# SIT210-_Project.net
KiCad netlist of a schematic drawn in EasyEDA
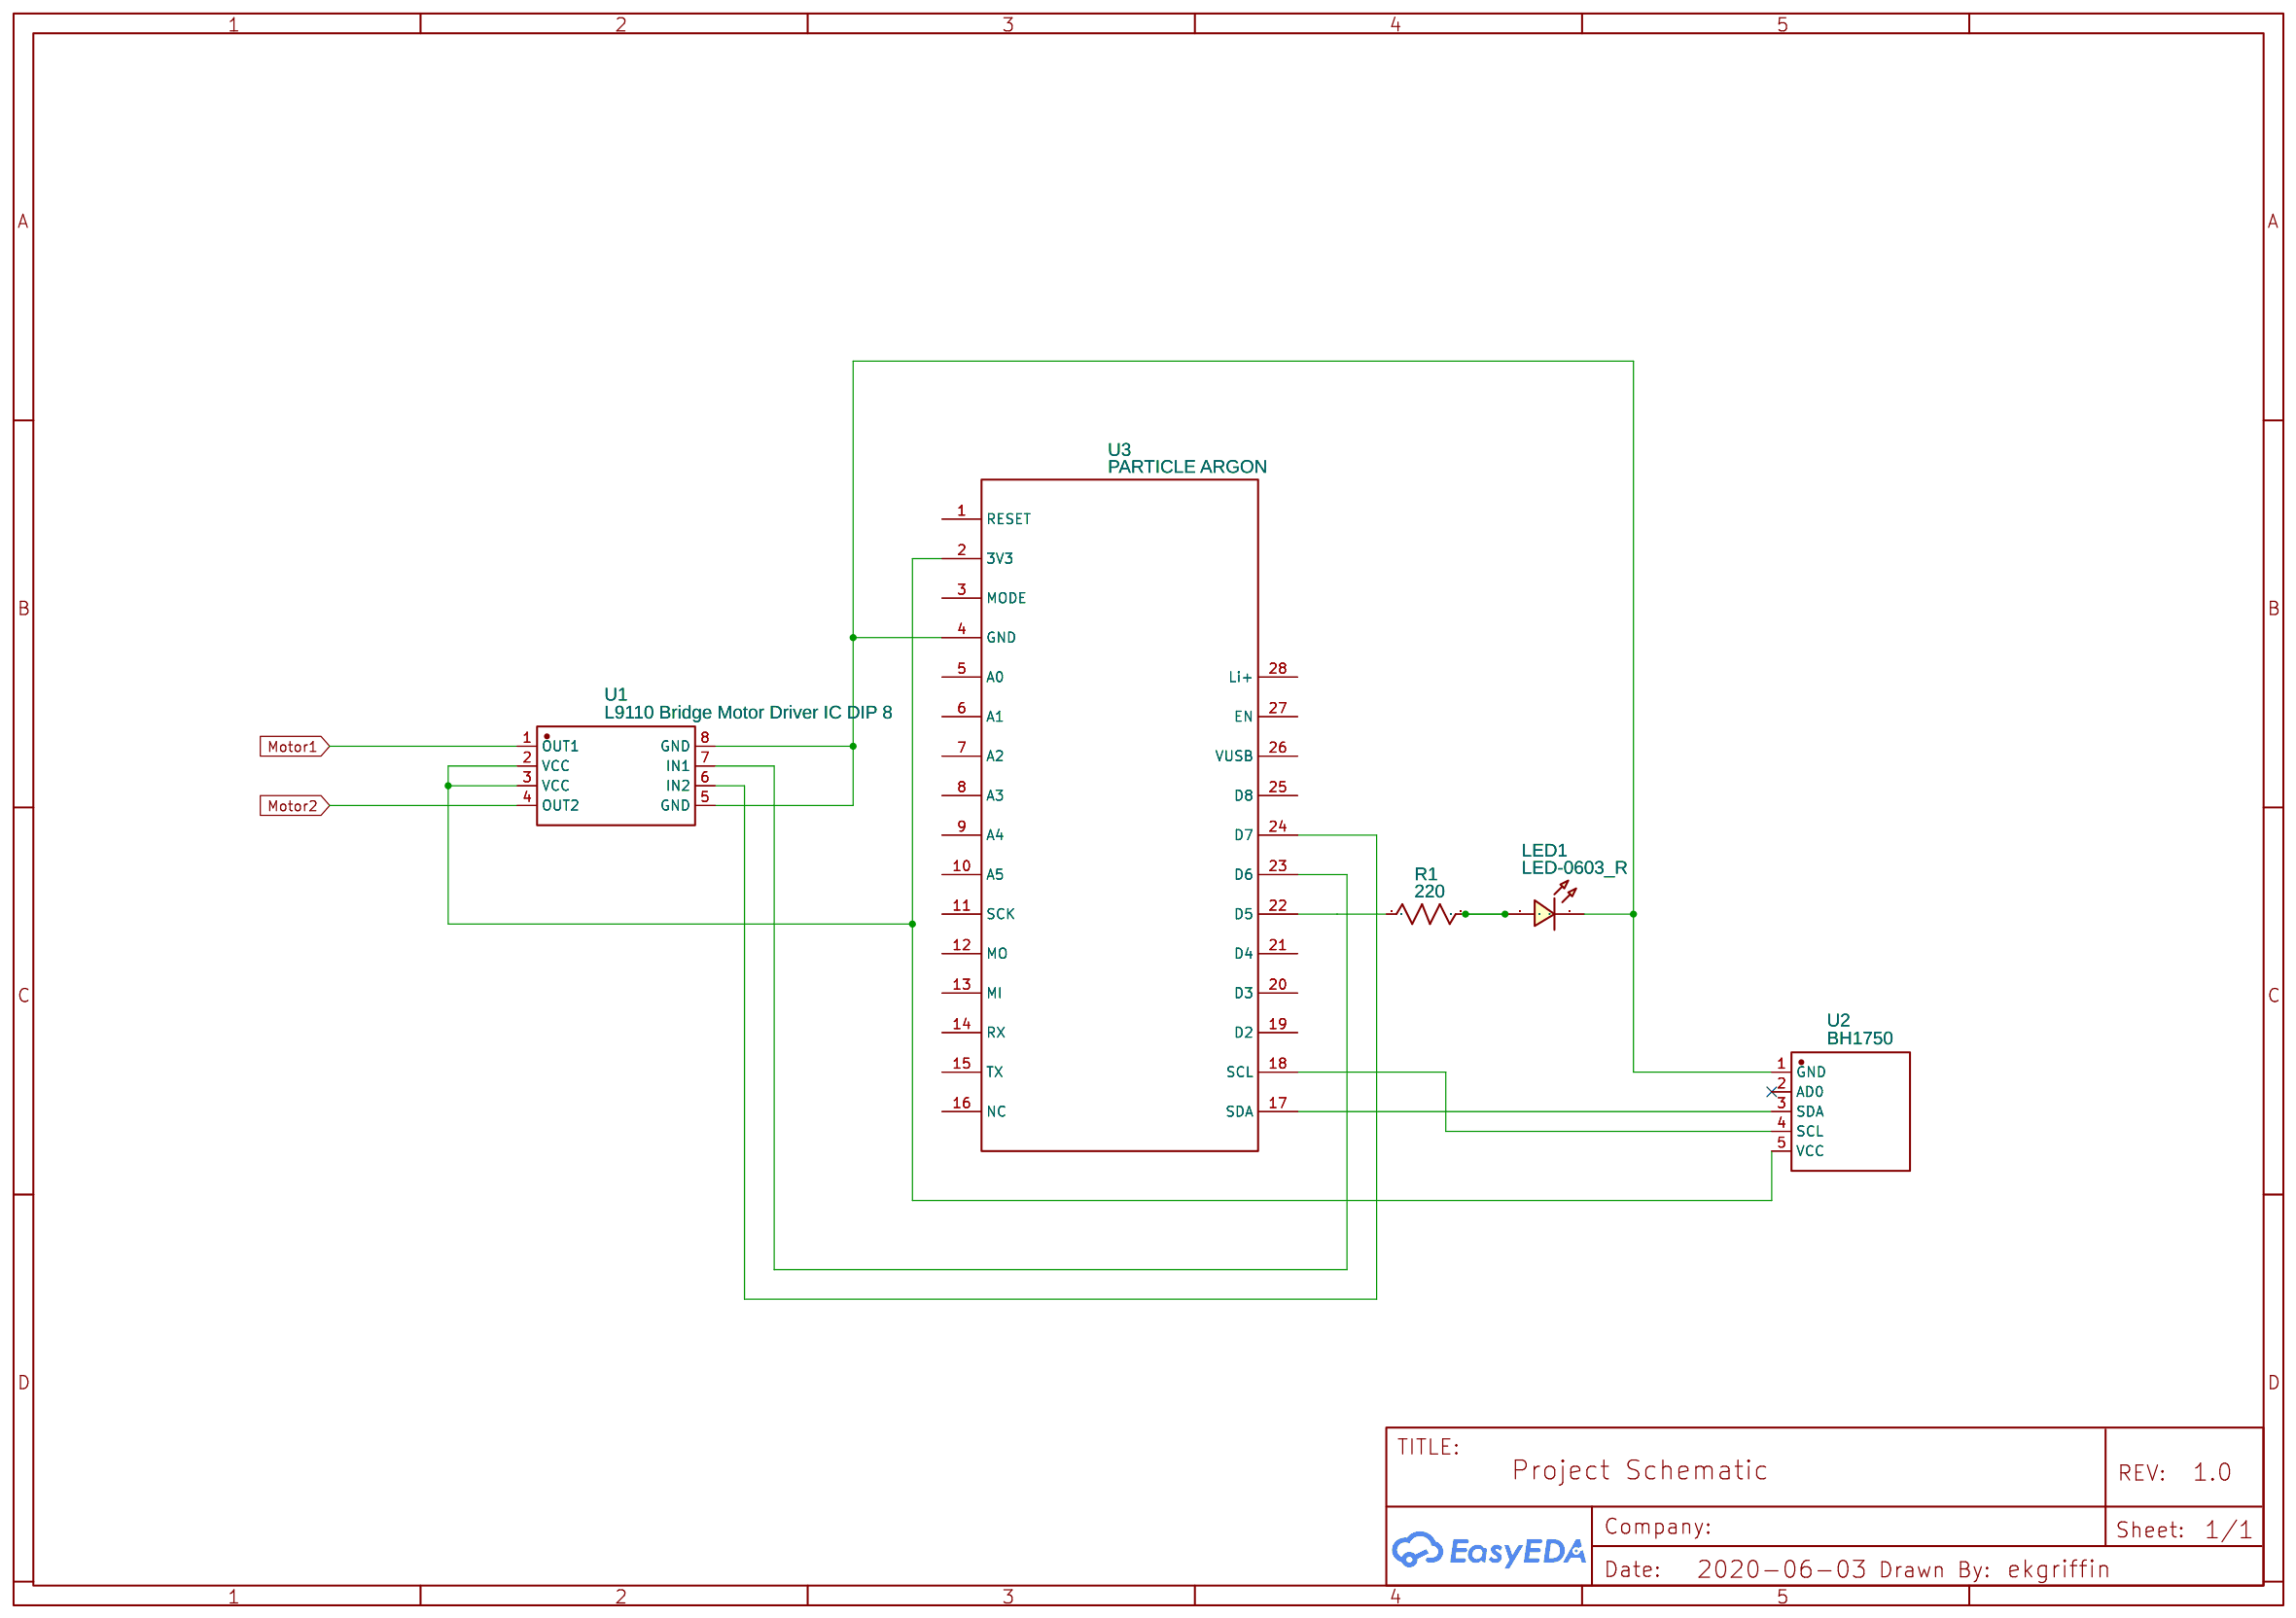
[diagram p0: schematic sheet]

(export (version "E")
  (design (tool "Eeschema 10.0.6"))
  (components
    (comp (ref "LED1")
      (value "LED-0603_R")
      (fields
        (field (name "BOM_Manufacturer Part") "19-217/R6C-AL1M2VY/3T")
        (field (name "BOM_Supplier Part") "C72044")
      )
      (libsource (lib "") (part "LED-0603_R"))
    )
    (comp (ref "R1") (value "220") (libsource (lib "") (part "R_0201_US")))
    (comp (ref "U1")
      (value "L9110 Bridge Motor Driver IC DIP 8")
      (fields (field (name "BOM_Manufacturer Part") "RJDR8837") (field (name "BOM_Supplier Part") "C490111"))
      (libsource (lib "") (part "L9110 Bridge Motor Driver IC DIP 8"))
    )
    (comp (ref "U2")
      (value "BH1750")
      (fields (field (name "BOM_Manufacturer Part") "New SchematicLib"))
      (libsource (lib "") (part "BH1750"))
    )
    (comp (ref "U3") (value "PARTICLE ARGON") (libsource (lib "") (part "PARTICLE ARGON")))
  )
  (nets
    (net (code "1") (name "Motor1") (class "Default")
      (node (ref "U1") (pin "1") (pinfunction "OUT1_1") (pintype "unspecified"))
    )
    (net (code "2") (name "Motor2") (class "Default")
      (node (ref "U1") (pin "4") (pinfunction "OUT2_4") (pintype "unspecified"))
    )
    (net (code "3") (name "Net-(LED1-Pad1)") (class "Default")
      (node (ref "LED1") (pin "1") (pinfunction "1_1") (pintype "unspecified"))
      (node (ref "R1") (pin "2") (pinfunction "2_2") (pintype "unspecified"))
    )
    (net (code "4") (name "Net-(U1-IN1)") (class "Default")
      (node (ref "U1") (pin "7") (pinfunction "IN1_7") (pintype "unspecified"))
      (node (ref "U3") (pin "23") (pinfunction "D6_23") (pintype "unspecified"))
    )
    (net (code "5") (name "Net-(U1-IN2)") (class "Default")
      (node (ref "U1") (pin "6") (pinfunction "IN2_6") (pintype "unspecified"))
      (node (ref "U3") (pin "24") (pinfunction "D7_24") (pintype "unspecified"))
    )
    (net (code "6") (name "Net-(U2-GND)") (class "Default")
      (node (ref "LED1") (pin "2") (pinfunction "2_2") (pintype "unspecified"))
      (node (ref "U1") (pin "5") (pinfunction "GND_5") (pintype "unspecified"))
      (node (ref "U1") (pin "8") (pinfunction "GND_8") (pintype "unspecified"))
      (node (ref "U2") (pin "1") (pinfunction "GND_1") (pintype "unspecified"))
      (node (ref "U3") (pin "4") (pinfunction "GND_4") (pintype "unspecified"))
    )
    (net (code "7") (name "Net-(U2-SCL)") (class "Default")
      (node (ref "U2") (pin "4") (pinfunction "SCL_4") (pintype "unspecified"))
      (node (ref "U3") (pin "18") (pinfunction "SCL_18") (pintype "unspecified"))
    )
    (net (code "8") (name "Net-(U2-SDA)") (class "Default")
      (node (ref "U2") (pin "3") (pinfunction "SDA_3") (pintype "unspecified"))
      (node (ref "U3") (pin "17") (pinfunction "SDA_17") (pintype "unspecified"))
    )
    (net (code "9") (name "Net-(U2-VCC)") (class "Default")
      (node (ref "U1") (pin "2") (pinfunction "VCC_2") (pintype "unspecified"))
      (node (ref "U1") (pin "3") (pinfunction "VCC_3") (pintype "unspecified"))
      (node (ref "U2") (pin "5") (pinfunction "VCC_5") (pintype "unspecified"))
      (node (ref "U3") (pin "2") (pinfunction "3V3_2") (pintype "unspecified"))
    )
    (net (code "10") (name "Net-(U3-D5)") (class "Default")
      (node (ref "R1") (pin "1") (pinfunction "1_1") (pintype "unspecified"))
      (node (ref "U3") (pin "22") (pinfunction "D5_22") (pintype "unspecified"))
    )
    (net (code "11") (name "unconnected-(U2-AD0-Pad2)") (class "Default")
      (node (ref "U2") (pin "2") (pinfunction "AD0_2") (pintype "unspecified+no_connect"))
    )
    (net (code "12") (name "unconnected-(U3-A0-Pad5)") (class "Default")
      (node (ref "U3") (pin "5") (pinfunction "A0_5") (pintype "unspecified"))
    )
    (net (code "13") (name "unconnected-(U3-A1-Pad6)") (class "Default")
      (node (ref "U3") (pin "6") (pinfunction "A1_6") (pintype "unspecified"))
    )
    (net (code "14") (name "unconnected-(U3-A2-Pad7)") (class "Default")
      (node (ref "U3") (pin "7") (pinfunction "A2_7") (pintype "unspecified"))
    )
    (net (code "15") (name "unconnected-(U3-A3-Pad8)") (class "Default")
      (node (ref "U3") (pin "8") (pinfunction "A3_8") (pintype "unspecified"))
    )
    (net (code "16") (name "unconnected-(U3-A4-Pad9)") (class "Default")
      (node (ref "U3") (pin "9") (pinfunction "A4_9") (pintype "unspecified"))
    )
    (net (code "17") (name "unconnected-(U3-A5-Pad10)") (class "Default")
      (node (ref "U3") (pin "10") (pinfunction "A5_10") (pintype "unspecified"))
    )
    (net (code "18") (name "unconnected-(U3-D2-Pad19)") (class "Default")
      (node (ref "U3") (pin "19") (pinfunction "D2_19") (pintype "unspecified"))
    )
    (net (code "19") (name "unconnected-(U3-D3-Pad20)") (class "Default")
      (node (ref "U3") (pin "20") (pinfunction "D3_20") (pintype "unspecified"))
    )
    (net (code "20") (name "unconnected-(U3-D4-Pad21)") (class "Default")
      (node (ref "U3") (pin "21") (pinfunction "D4_21") (pintype "unspecified"))
    )
    (net (code "21") (name "unconnected-(U3-D8-Pad25)") (class "Default")
      (node (ref "U3") (pin "25") (pinfunction "D8_25") (pintype "unspecified"))
    )
    (net (code "22") (name "unconnected-(U3-EN-Pad27)") (class "Default")
      (node (ref "U3") (pin "27") (pinfunction "EN_27") (pintype "unspecified"))
    )
    (net (code "23") (name "unconnected-(U3-Li+-Pad28)") (class "Default")
      (node (ref "U3") (pin "28") (pinfunction "Li+_28") (pintype "unspecified"))
    )
    (net (code "24") (name "unconnected-(U3-MI-Pad13)") (class "Default")
      (node (ref "U3") (pin "13") (pinfunction "MI_13") (pintype "unspecified"))
    )
    (net (code "25") (name "unconnected-(U3-MO-Pad12)") (class "Default")
      (node (ref "U3") (pin "12") (pinfunction "MO_12") (pintype "unspecified"))
    )
    (net (code "26") (name "unconnected-(U3-MODE-Pad3)") (class "Default")
      (node (ref "U3") (pin "3") (pinfunction "MODE_3") (pintype "unspecified"))
    )
    (net (code "27") (name "unconnected-(U3-NC-Pad16)") (class "Default")
      (node (ref "U3") (pin "16") (pinfunction "NC_16") (pintype "unspecified"))
    )
    (net (code "28") (name "unconnected-(U3-RESET-Pad1)") (class "Default")
      (node (ref "U3") (pin "1") (pinfunction "RESET_1") (pintype "unspecified"))
    )
    (net (code "29") (name "unconnected-(U3-RX-Pad14)") (class "Default")
      (node (ref "U3") (pin "14") (pinfunction "RX_14") (pintype "unspecified"))
    )
    (net (code "30") (name "unconnected-(U3-SCK-Pad11)") (class "Default")
      (node (ref "U3") (pin "11") (pinfunction "SCK_11") (pintype "unspecified"))
    )
    (net (code "31") (name "unconnected-(U3-TX-Pad15)") (class "Default")
      (node (ref "U3") (pin "15") (pinfunction "TX_15") (pintype "unspecified"))
    )
    (net (code "32") (name "unconnected-(U3-VUSB-Pad26)") (class "Default")
      (node (ref "U3") (pin "26") (pinfunction "VUSB_26") (pintype "unspecified"))
    )
  )
)
